# Sheet1.net
KiCad netlist of a schematic drawn in Altium Designer
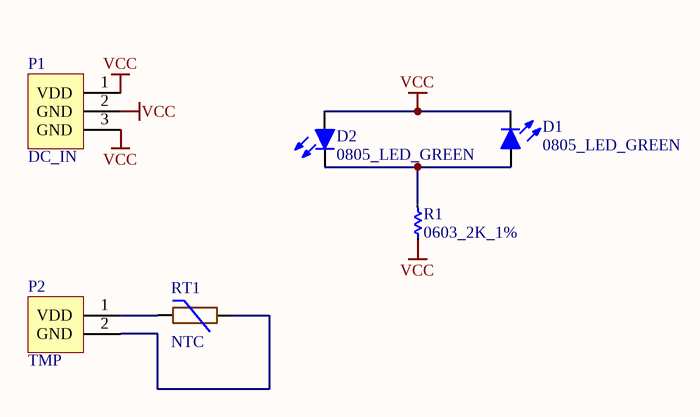
[diagram p0: Sheet1.SchDoc]

(export (version "E")
  (design (tool "Eeschema 10.0.6"))
  (components
    (comp (ref "D1")
      (value "0805_LED_GREEN")
      (footprint "LED0805G")
      (libsource (lib "Schlib1") (part "LED0805"))
    )
    (comp (ref "D2")
      (value "0805_LED_GREEN")
      (footprint "LED0805G")
      (libsource (lib "Schlib1") (part "LED0805"))
    )
    (comp (ref "P1") (value "DC_IN") (footprint "DC_IN") (libsource (lib "Schlib1") (part "DC_IN")))
    (comp (ref "P2") (value "TMP") (footprint "TMP_IN") (libsource (lib "Schlib1") (part "TMP_IN")))
    (comp (ref "R1")
      (value "0603_2K_1%")
      (footprint "R0603")
      (description "Resistor")
      (fields (field (name "PUBLISHER") "Altium Limited"))
      (libsource (lib "Schlib1") (part "R0603"))
    )
    (comp (ref "RT1")
      (value "NTC")
      (footprint "NTC0805")
      (libsource (lib "Schlib1") (part "NTCG204CH104JT1S"))
    )
  )
  (nets
    (net (code "1") (name "Net-(D1-A)") (class "Default")
      (node (ref "D1") (pin "1") (pinfunction "A_1") (pintype "passive"))
      (node (ref "D2") (pin "2") (pinfunction "K_2") (pintype "passive"))
      (node (ref "R1") (pin "2") (pinfunction "2_2") (pintype "passive"))
    )
    (net (code "2") (name "Net-(P2-GND)") (class "Default")
      (node (ref "P2") (pin "2") (pinfunction "GND_2") (pintype "passive"))
      (node (ref "RT1") (pin "2") (pinfunction "2_2") (pintype "passive"))
    )
    (net (code "3") (name "Net-(P2-VDD)") (class "Default")
      (node (ref "P2") (pin "1") (pinfunction "VDD_1") (pintype "passive"))
      (node (ref "RT1") (pin "1") (pinfunction "1_1") (pintype "passive"))
    )
    (net (code "4") (name "VCC") (class "Default")
      (node (ref "D1") (pin "2") (pinfunction "K_2") (pintype "passive"))
      (node (ref "D2") (pin "1") (pinfunction "A_1") (pintype "passive"))
      (node (ref "P1") (pin "1") (pinfunction "VDD_1") (pintype "passive"))
      (node (ref "P1") (pin "2") (pinfunction "GND_2") (pintype "passive"))
      (node (ref "P1") (pin "3") (pinfunction "GND_3") (pintype "passive"))
      (node (ref "R1") (pin "1") (pinfunction "1_1") (pintype "passive"))
    )
  )
)
